# New_Project.net
KiCad netlist of a schematic drawn in EasyEDA
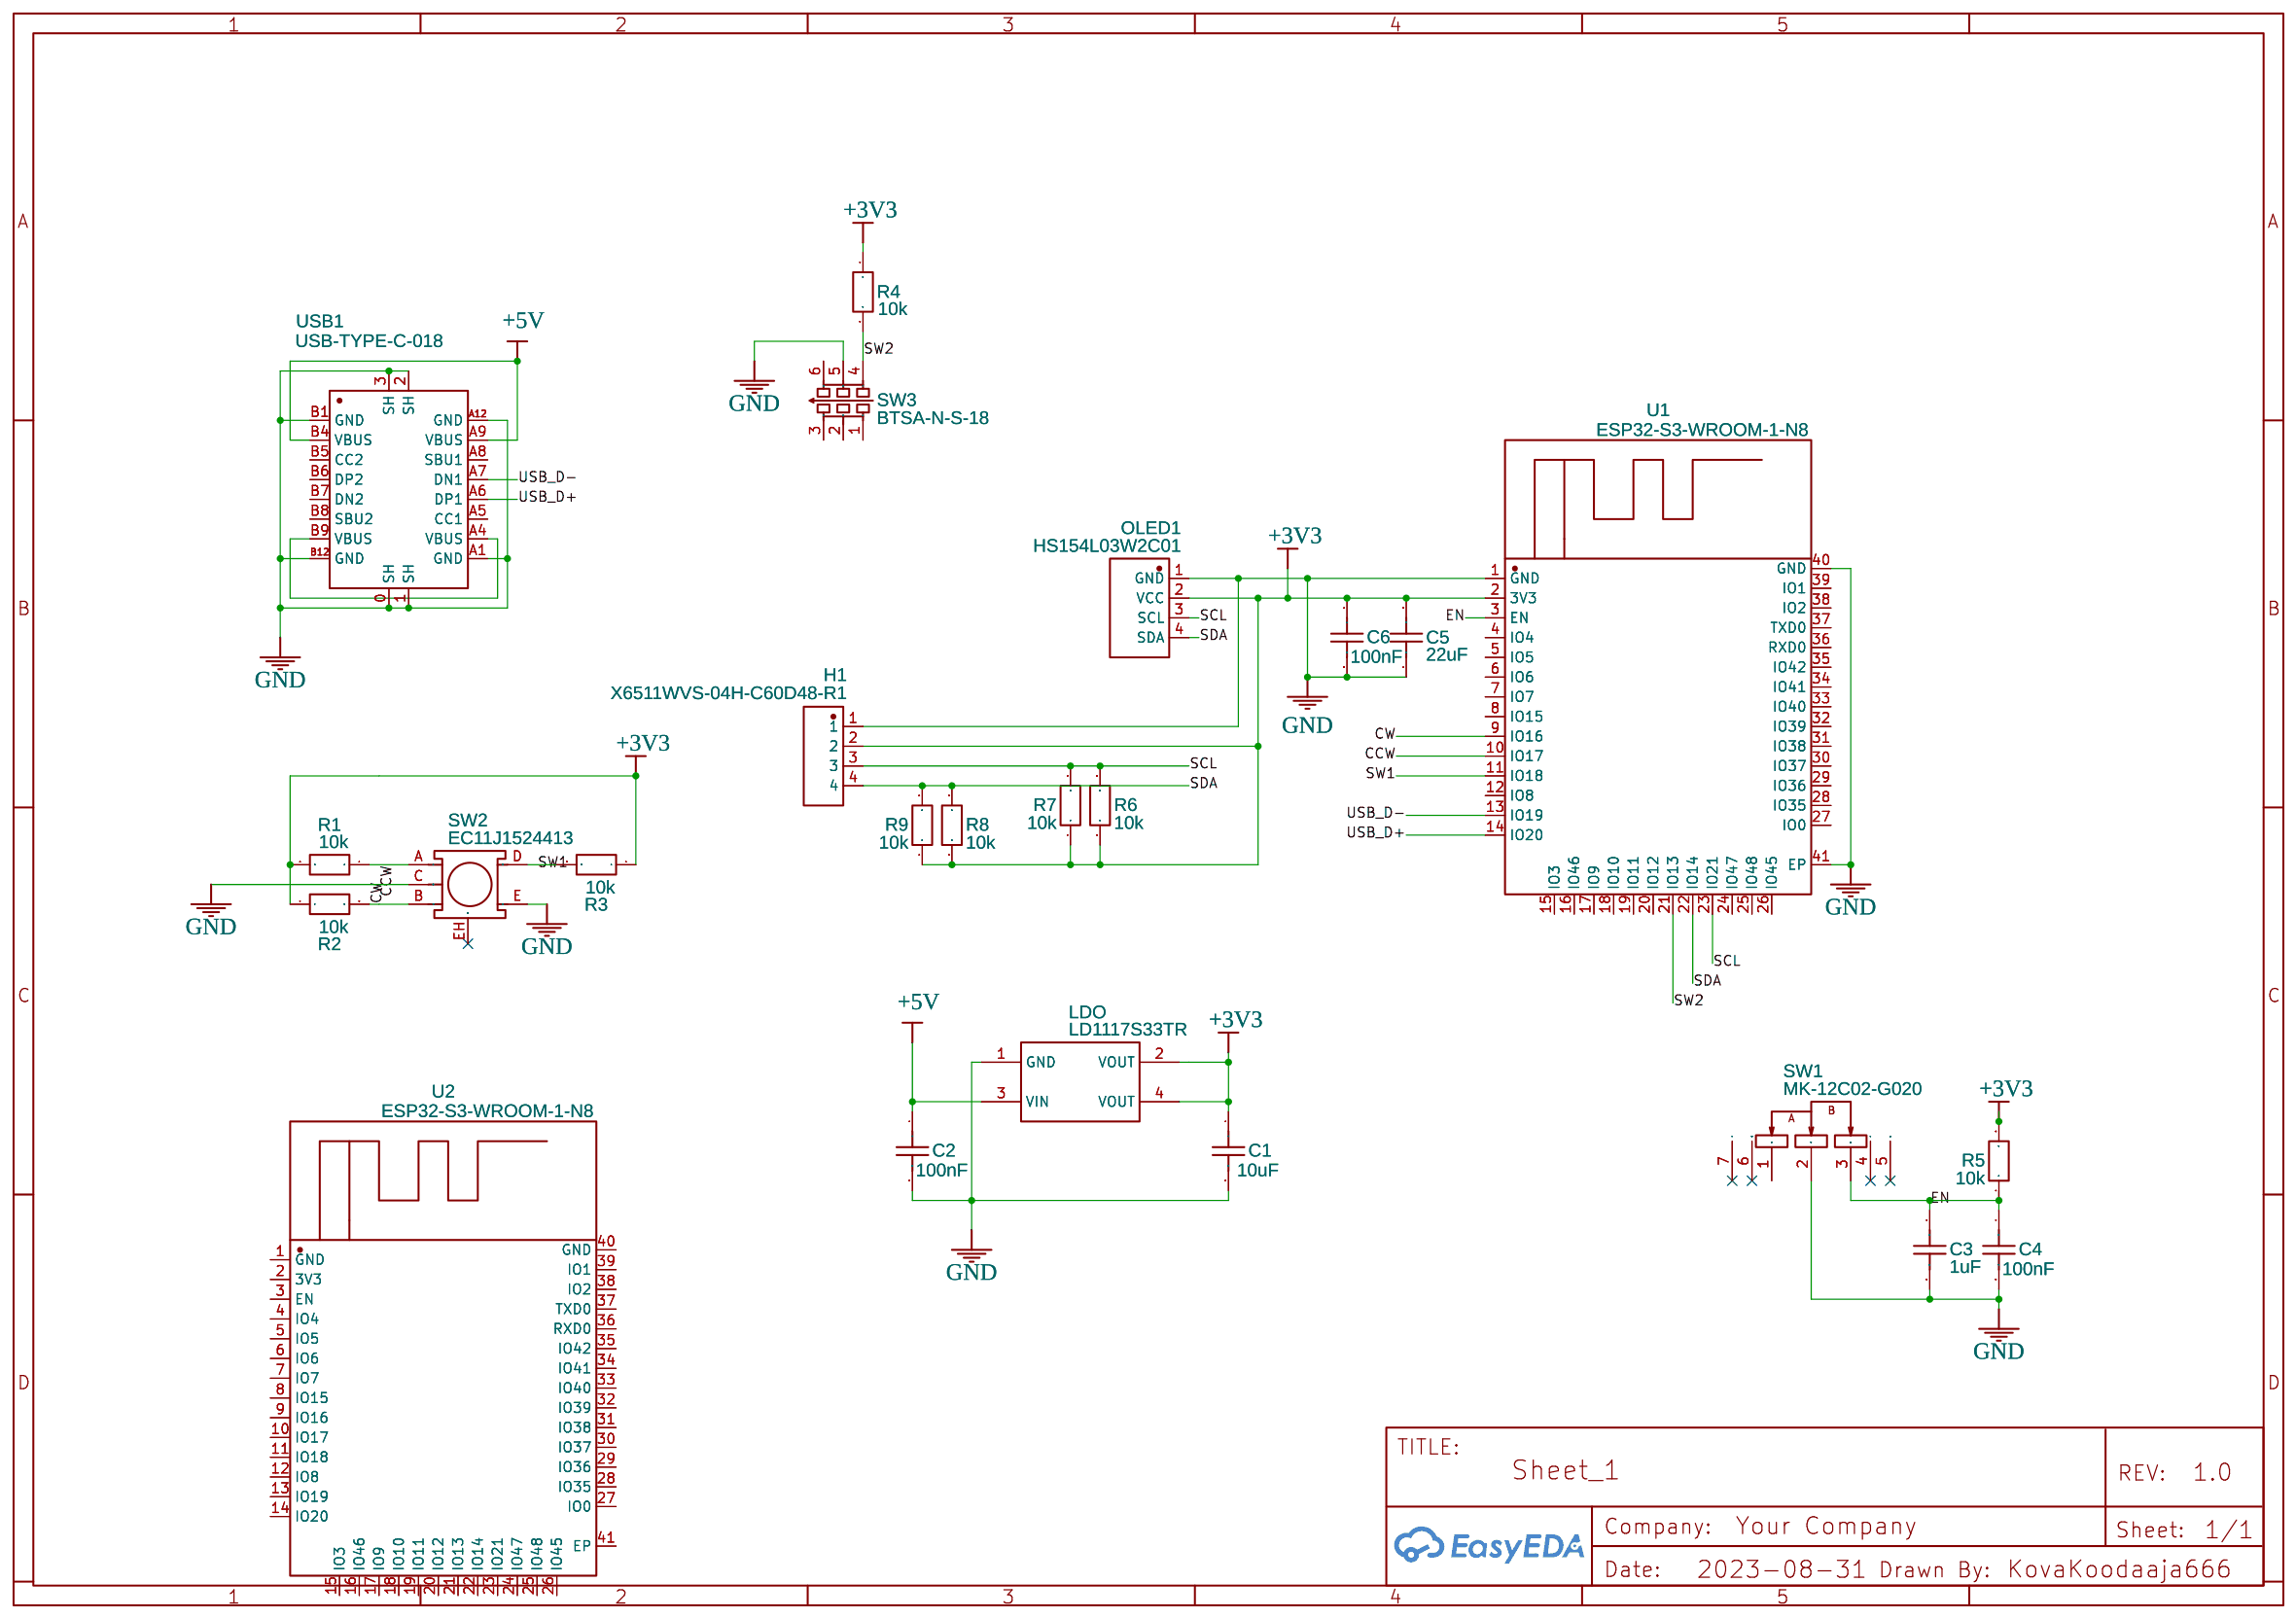
[diagram p0: schematic sheet]

(export (version "E")
  (design (tool "Eeschema 10.0.6"))
  (components
    (comp (ref "C1")
      (value "10uF")
      (fields
        (field (name "Manufacturer Part") "TCC0805X5R106K100FT")
        (field (name "Manufacturer") "CCTC(三环)")
      )
      (libsource (lib "") (part "TCC0805X5R106K100FT"))
    )
    (comp (ref "C2")
      (value "100nF")
      (fields (field (name "Manufacturer Part") "C0805B104K500NT") (field (name "Manufacturer") "TORCH(火炬)"))
      (libsource (lib "") (part "C0805B104K500NT"))
    )
    (comp (ref "C3")
      (value "1uF")
      (fields (field (name "Manufacturer") "FH(风华)"))
      (libsource (lib "") (part "0805B105K500NT_C215803"))
    )
    (comp (ref "C4")
      (value "100nF")
      (fields (field (name "Manufacturer Part") "C0805B104K500NT") (field (name "Manufacturer") "TORCH(火炬)"))
      (libsource (lib "") (part "C0805B104K500NT"))
    )
    (comp (ref "C5")
      (value "22uF")
      (fields
        (field (name "Manufacturer Part") "TCC0805X5R226M100FT")
        (field (name "Manufacturer") "CCTC(三环)")
      )
      (libsource (lib "") (part "TCC0805X5R226M100FT"))
    )
    (comp (ref "C6")
      (value "100nF")
      (fields (field (name "Manufacturer Part") "C0805B104K500NT") (field (name "Manufacturer") "TORCH(火炬)"))
      (libsource (lib "") (part "C0805B104K500NT"))
    )
    (comp (ref "H1")
      (value "X6511WVS-04H-C60D48-R1")
      (fields
        (field (name "Manufacturer Part") "X6511WVS-04H-C60D48R1")
        (field (name "Manufacturer") "XKB Connectivity(中国星坤)")
      )
      (libsource (lib "") (part "X6511WVS-04H-C60D48-R1"))
    )
    (comp (ref "LDO")
      (value "LD1117S33TR")
      (fields (field (name "Manufacturer") "ST(意法半导体)"))
      (libsource (lib "") (part "LD1117S33TR"))
    )
    (comp (ref "OLED1")
      (value "HS154L03W2C01")
      (fields (field (name "Manufacturer") "HS(汉昇)"))
      (libsource (lib "") (part "HS154L03W2C01"))
    )
    (comp (ref "R1")
      (value "10k")
      (fields (field (name "Manufacturer Part") "FRC0603J103TS") (field (name "Manufacturer") "FOJAN(富捷)"))
      (libsource (lib "") (part "FRC0603J103TS_3"))
    )
    (comp (ref "R2")
      (value "10k")
      (fields (field (name "Manufacturer Part") "FRC0603J103TS") (field (name "Manufacturer") "FOJAN(富捷)"))
      (libsource (lib "") (part "FRC0603J103TS_1"))
    )
    (comp (ref "R3")
      (value "10k")
      (fields (field (name "Manufacturer Part") "FRC0603J103TS") (field (name "Manufacturer") "FOJAN(富捷)"))
      (libsource (lib "") (part "FRC0603J103TS_3"))
    )
    (comp (ref "R4")
      (value "10k")
      (fields (field (name "Manufacturer Part") "FRC0603J103TS") (field (name "Manufacturer") "FOJAN(富捷)"))
      (libsource (lib "") (part "FRC0603J103TS"))
    )
    (comp (ref "R5")
      (value "10k")
      (fields (field (name "Manufacturer Part") "FRC0603J103TS") (field (name "Manufacturer") "FOJAN(富捷)"))
      (libsource (lib "") (part "FRC0603J103TS_2"))
    )
    (comp (ref "R6")
      (value "10k")
      (fields (field (name "Manufacturer Part") "FRC0603J103TS") (field (name "Manufacturer") "FOJAN(富捷)"))
      (libsource (lib "") (part "FRC0603J103TS_2"))
    )
    (comp (ref "R7")
      (value "10k")
      (fields (field (name "Manufacturer Part") "FRC0603J103TS") (field (name "Manufacturer") "FOJAN(富捷)"))
      (libsource (lib "") (part "FRC0603J103TS_2"))
    )
    (comp (ref "R8")
      (value "10k")
      (fields (field (name "Manufacturer Part") "FRC0603J103TS") (field (name "Manufacturer") "FOJAN(富捷)"))
      (libsource (lib "") (part "FRC0603J103TS_2"))
    )
    (comp (ref "R9")
      (value "10k")
      (fields (field (name "Manufacturer Part") "FRC0603J103TS") (field (name "Manufacturer") "FOJAN(富捷)"))
      (libsource (lib "") (part "FRC0603J103TS_2"))
    )
    (comp (ref "SW1")
      (value "MK-12C02-G020")
      (fields (field (name "Manufacturer") "G-Switch"))
      (libsource (lib "") (part "MK-12C02-G020"))
    )
    (comp (ref "SW2")
      (value "EC11J1524413")
      (fields (field (name "Manufacturer") "ALPSALPINE(阿尔卑斯阿尔派)"))
      (libsource (lib "") (part "EC11J1524413"))
    )
    (comp (ref "SW3")
      (value "BTSA-N-S-18")
      (fields (field (name "Manufacturer") "ROCPU Switches(台普)"))
      (libsource (lib "") (part "BTSA-N-S-18"))
    )
    (comp (ref "U1")
      (value "ESP32-S3-WROOM-1-N8")
      (fields (field (name "Manufacturer") "ESPRESSIF(乐鑫)"))
      (libsource (lib "") (part "ESP32-S3-WROOM-1-N8"))
    )
    (comp (ref "U2")
      (value "ESP32-S3-WROOM-1-N8")
      (fields (field (name "Manufacturer") "ESPRESSIF(乐鑫)"))
      (libsource (lib "") (part "ESP32-S3-WROOM-1-N8"))
    )
    (comp (ref "USB1")
      (value "USB-TYPE-C-018")
      (fields (field (name "Manufacturer") "DEALON(德艺隆)"))
      (libsource (lib "") (part "USB-TYPE-C-018"))
    )
  )
  (nets
    (net (code "1") (name "+3V3") (class "Default")
      (node (ref "C1") (pin "1") (pinfunction "1_1") (pintype "unspecified"))
      (node (ref "C5") (pin "2") (pinfunction "2_2") (pintype "unspecified"))
      (node (ref "C6") (pin "1") (pinfunction "1_1") (pintype "unspecified"))
      (node (ref "H1") (pin "2") (pinfunction "2_2") (pintype "unspecified"))
      (node (ref "LDO") (pin "2") (pinfunction "VOUT_2") (pintype "unspecified"))
      (node (ref "LDO") (pin "4") (pinfunction "VOUT_4") (pintype "unspecified"))
      (node (ref "OLED1") (pin "2") (pinfunction "VCC_2") (pintype "unspecified"))
      (node (ref "R1") (pin "2") (pinfunction "2_2") (pintype "unspecified"))
      (node (ref "R2") (pin "1") (pinfunction "1_1") (pintype "unspecified"))
      (node (ref "R3") (pin "1") (pinfunction "1_1") (pintype "unspecified"))
      (node (ref "R4") (pin "1") (pinfunction "1_1") (pintype "unspecified"))
      (node (ref "R5") (pin "2") (pinfunction "2_2") (pintype "unspecified"))
      (node (ref "R6") (pin "1") (pinfunction "1_1") (pintype "unspecified"))
      (node (ref "R7") (pin "1") (pinfunction "1_1") (pintype "unspecified"))
      (node (ref "R8") (pin "1") (pinfunction "1_1") (pintype "unspecified"))
      (node (ref "R9") (pin "1") (pinfunction "1_1") (pintype "unspecified"))
      (node (ref "U1") (pin "2") (pinfunction "3V3_2") (pintype "unspecified"))
    )
    (net (code "2") (name "+5V") (class "Default")
      (node (ref "C2") (pin "1") (pinfunction "1_1") (pintype "unspecified"))
      (node (ref "LDO") (pin "3") (pinfunction "VIN_3") (pintype "unspecified"))
      (node (ref "USB1") (pin "A9") (pinfunction "VBUS_A9") (pintype "unspecified"))
      (node (ref "USB1") (pin "B4") (pinfunction "VBUS_B4") (pintype "unspecified"))
    )
    (net (code "3") (name "/CCW") (class "Default")
      (node (ref "R1") (pin "1") (pinfunction "1_1") (pintype "unspecified"))
      (node (ref "SW2") (pin "A") (pinfunction "A_A") (pintype "unspecified"))
      (node (ref "U1") (pin "10") (pinfunction "IO17_10") (pintype "unspecified"))
    )
    (net (code "4") (name "/CW") (class "Default")
      (node (ref "R2") (pin "2") (pinfunction "2_2") (pintype "unspecified"))
      (node (ref "SW2") (pin "B") (pinfunction "B_B") (pintype "unspecified"))
      (node (ref "U1") (pin "9") (pinfunction "IO16_9") (pintype "unspecified"))
    )
    (net (code "5") (name "/EN") (class "Default")
      (node (ref "C3") (pin "1") (pinfunction "1_1") (pintype "unspecified"))
      (node (ref "C4") (pin "1") (pinfunction "1_1") (pintype "unspecified"))
      (node (ref "R5") (pin "1") (pinfunction "1_1") (pintype "unspecified"))
      (node (ref "SW1") (pin "3") (pinfunction "3_3") (pintype "unspecified"))
      (node (ref "U1") (pin "3") (pinfunction "EN_3") (pintype "unspecified"))
    )
    (net (code "6") (name "/SCL") (class "Default")
      (node (ref "H1") (pin "3") (pinfunction "3_3") (pintype "unspecified"))
      (node (ref "OLED1") (pin "3") (pinfunction "SCL_3") (pintype "unspecified"))
      (node (ref "R6") (pin "2") (pinfunction "2_2") (pintype "unspecified"))
      (node (ref "R7") (pin "2") (pinfunction "2_2") (pintype "unspecified"))
      (node (ref "U1") (pin "23") (pinfunction "IO21_23") (pintype "unspecified"))
    )
    (net (code "7") (name "/SDA") (class "Default")
      (node (ref "H1") (pin "4") (pinfunction "4_4") (pintype "unspecified"))
      (node (ref "OLED1") (pin "4") (pinfunction "SDA_4") (pintype "unspecified"))
      (node (ref "R8") (pin "2") (pinfunction "2_2") (pintype "unspecified"))
      (node (ref "R9") (pin "2") (pinfunction "2_2") (pintype "unspecified"))
      (node (ref "U1") (pin "22") (pinfunction "IO14_22") (pintype "unspecified"))
    )
    (net (code "8") (name "/SW1") (class "Default")
      (node (ref "R3") (pin "2") (pinfunction "2_2") (pintype "unspecified"))
      (node (ref "SW2") (pin "D") (pinfunction "D_D") (pintype "unspecified"))
      (node (ref "U1") (pin "11") (pinfunction "IO18_11") (pintype "unspecified"))
    )
    (net (code "9") (name "/SW2") (class "Default")
      (node (ref "R4") (pin "2") (pinfunction "2_2") (pintype "unspecified"))
      (node (ref "SW3") (pin "4") (pinfunction "4_4") (pintype "unspecified"))
      (node (ref "U1") (pin "21") (pinfunction "IO13_21") (pintype "unspecified"))
    )
    (net (code "10") (name "/USB_D+") (class "Default")
      (node (ref "U1") (pin "14") (pinfunction "IO20_14") (pintype "unspecified"))
      (node (ref "USB1") (pin "A6") (pinfunction "DP1_A6") (pintype "unspecified"))
    )
    (net (code "11") (name "/USB_D-") (class "Default")
      (node (ref "U1") (pin "13") (pinfunction "IO19_13") (pintype "unspecified"))
      (node (ref "USB1") (pin "A7") (pinfunction "DN1_A7") (pintype "unspecified"))
    )
    (net (code "12") (name "GND") (class "Default")
      (node (ref "C1") (pin "2") (pinfunction "2_2") (pintype "unspecified"))
      (node (ref "C2") (pin "2") (pinfunction "2_2") (pintype "unspecified"))
      (node (ref "C3") (pin "2") (pinfunction "2_2") (pintype "unspecified"))
      (node (ref "C4") (pin "2") (pinfunction "2_2") (pintype "unspecified"))
      (node (ref "C5") (pin "1") (pinfunction "1_1") (pintype "unspecified"))
      (node (ref "C6") (pin "2") (pinfunction "2_2") (pintype "unspecified"))
      (node (ref "H1") (pin "1") (pinfunction "1_1") (pintype "unspecified"))
      (node (ref "LDO") (pin "1") (pinfunction "GND_1") (pintype "unspecified"))
      (node (ref "OLED1") (pin "1") (pinfunction "GND_1") (pintype "unspecified"))
      (node (ref "SW1") (pin "2") (pinfunction "2_2") (pintype "unspecified"))
      (node (ref "SW2") (pin "C") (pinfunction "C_C") (pintype "unspecified"))
      (node (ref "SW2") (pin "E") (pinfunction "E_E") (pintype "unspecified"))
      (node (ref "SW3") (pin "5") (pinfunction "5_5") (pintype "unspecified"))
      (node (ref "U1") (pin "1") (pinfunction "GND_1") (pintype "unspecified"))
      (node (ref "U1") (pin "40") (pinfunction "GND_40") (pintype "unspecified"))
      (node (ref "U1") (pin "41") (pinfunction "EP_41") (pintype "unspecified"))
      (node (ref "USB1") (pin "0") (pinfunction "SH_0") (pintype "unspecified"))
      (node (ref "USB1") (pin "1") (pinfunction "SH_1") (pintype "unspecified"))
      (node (ref "USB1") (pin "2") (pinfunction "SH_2") (pintype "unspecified"))
      (node (ref "USB1") (pin "3") (pinfunction "SH_3") (pintype "unspecified"))
      (node (ref "USB1") (pin "A1") (pinfunction "GND_A1") (pintype "unspecified"))
      (node (ref "USB1") (pin "A12") (pinfunction "GND_A12") (pintype "unspecified"))
      (node (ref "USB1") (pin "B1") (pinfunction "GND_B1") (pintype "unspecified"))
      (node (ref "USB1") (pin "B12") (pinfunction "GND_B12") (pintype "unspecified"))
    )
    (net (code "13") (name "Net-(USB1-VBUS-PadA4)") (class "Default")
      (node (ref "USB1") (pin "A4") (pinfunction "VBUS_A4") (pintype "unspecified"))
      (node (ref "USB1") (pin "B9") (pinfunction "VBUS_B9") (pintype "unspecified"))
    )
    (net (code "14") (name "unconnected-(SW1-Pad1)") (class "Default")
      (node (ref "SW1") (pin "1") (pinfunction "1_1") (pintype "unspecified"))
    )
    (net (code "15") (name "unconnected-(SW1-Pad4)") (class "Default")
      (node (ref "SW1") (pin "4") (pinfunction "4_4") (pintype "unspecified+no_connect"))
    )
    (net (code "16") (name "unconnected-(SW1-Pad5)") (class "Default")
      (node (ref "SW1") (pin "5") (pinfunction "5_5") (pintype "unspecified+no_connect"))
    )
    (net (code "17") (name "unconnected-(SW1-Pad6)") (class "Default")
      (node (ref "SW1") (pin "6") (pinfunction "6_6") (pintype "unspecified+no_connect"))
    )
    (net (code "18") (name "unconnected-(SW1-Pad7)") (class "Default")
      (node (ref "SW1") (pin "7") (pinfunction "7_7") (pintype "unspecified+no_connect"))
    )
    (net (code "19") (name "unconnected-(SW2-PadEH)") (class "Default")
      (node (ref "SW2") (pin "EH") (pinfunction "EH_EH") (pintype "unspecified+no_connect"))
    )
    (net (code "20") (name "unconnected-(SW3-Pad1)") (class "Default")
      (node (ref "SW3") (pin "1") (pinfunction "1_1") (pintype "unspecified"))
    )
    (net (code "21") (name "unconnected-(SW3-Pad2)") (class "Default")
      (node (ref "SW3") (pin "2") (pinfunction "2_2") (pintype "unspecified"))
    )
    (net (code "22") (name "unconnected-(SW3-Pad3)") (class "Default")
      (node (ref "SW3") (pin "3") (pinfunction "3_3") (pintype "unspecified"))
    )
    (net (code "23") (name "unconnected-(SW3-Pad6)") (class "Default")
      (node (ref "SW3") (pin "6") (pinfunction "6_6") (pintype "unspecified"))
    )
    (net (code "24") (name "unconnected-(U1-IO0-Pad27)") (class "Default")
      (node (ref "U1") (pin "27") (pinfunction "IO0_27") (pintype "unspecified"))
    )
    (net (code "25") (name "unconnected-(U1-IO1-Pad39)") (class "Default")
      (node (ref "U1") (pin "39") (pinfunction "IO1_39") (pintype "unspecified"))
    )
    (net (code "26") (name "unconnected-(U1-IO2-Pad38)") (class "Default")
      (node (ref "U1") (pin "38") (pinfunction "IO2_38") (pintype "unspecified"))
    )
    (net (code "27") (name "unconnected-(U1-IO3-Pad15)") (class "Default")
      (node (ref "U1") (pin "15") (pinfunction "IO3_15") (pintype "unspecified"))
    )
    (net (code "28") (name "unconnected-(U1-IO4-Pad4)") (class "Default")
      (node (ref "U1") (pin "4") (pinfunction "IO4_4") (pintype "unspecified"))
    )
    (net (code "29") (name "unconnected-(U1-IO5-Pad5)") (class "Default")
      (node (ref "U1") (pin "5") (pinfunction "IO5_5") (pintype "unspecified"))
    )
    (net (code "30") (name "unconnected-(U1-IO6-Pad6)") (class "Default")
      (node (ref "U1") (pin "6") (pinfunction "IO6_6") (pintype "unspecified"))
    )
    (net (code "31") (name "unconnected-(U1-IO7-Pad7)") (class "Default")
      (node (ref "U1") (pin "7") (pinfunction "IO7_7") (pintype "unspecified"))
    )
    (net (code "32") (name "unconnected-(U1-IO8-Pad12)") (class "Default")
      (node (ref "U1") (pin "12") (pinfunction "IO8_12") (pintype "unspecified"))
    )
    (net (code "33") (name "unconnected-(U1-IO9-Pad17)") (class "Default")
      (node (ref "U1") (pin "17") (pinfunction "IO9_17") (pintype "unspecified"))
    )
    (net (code "34") (name "unconnected-(U1-IO10-Pad18)") (class "Default")
      (node (ref "U1") (pin "18") (pinfunction "IO10_18") (pintype "unspecified"))
    )
    (net (code "35") (name "unconnected-(U1-IO11-Pad19)") (class "Default")
      (node (ref "U1") (pin "19") (pinfunction "IO11_19") (pintype "unspecified"))
    )
    (net (code "36") (name "unconnected-(U1-IO12-Pad20)") (class "Default")
      (node (ref "U1") (pin "20") (pinfunction "IO12_20") (pintype "unspecified"))
    )
    (net (code "37") (name "unconnected-(U1-IO15-Pad8)") (class "Default")
      (node (ref "U1") (pin "8") (pinfunction "IO15_8") (pintype "unspecified"))
    )
    (net (code "38") (name "unconnected-(U1-IO35-Pad28)") (class "Default")
      (node (ref "U1") (pin "28") (pinfunction "IO35_28") (pintype "unspecified"))
    )
    (net (code "39") (name "unconnected-(U1-IO36-Pad29)") (class "Default")
      (node (ref "U1") (pin "29") (pinfunction "IO36_29") (pintype "unspecified"))
    )
    (net (code "40") (name "unconnected-(U1-IO37-Pad30)") (class "Default")
      (node (ref "U1") (pin "30") (pinfunction "IO37_30") (pintype "unspecified"))
    )
    (net (code "41") (name "unconnected-(U1-IO38-Pad31)") (class "Default")
      (node (ref "U1") (pin "31") (pinfunction "IO38_31") (pintype "unspecified"))
    )
    (net (code "42") (name "unconnected-(U1-IO39-Pad32)") (class "Default")
      (node (ref "U1") (pin "32") (pinfunction "IO39_32") (pintype "unspecified"))
    )
    (net (code "43") (name "unconnected-(U1-IO40-Pad33)") (class "Default")
      (node (ref "U1") (pin "33") (pinfunction "IO40_33") (pintype "unspecified"))
    )
    (net (code "44") (name "unconnected-(U1-IO41-Pad34)") (class "Default")
      (node (ref "U1") (pin "34") (pinfunction "IO41_34") (pintype "unspecified"))
    )
    (net (code "45") (name "unconnected-(U1-IO42-Pad35)") (class "Default")
      (node (ref "U1") (pin "35") (pinfunction "IO42_35") (pintype "unspecified"))
    )
    (net (code "46") (name "unconnected-(U1-IO45-Pad26)") (class "Default")
      (node (ref "U1") (pin "26") (pinfunction "IO45_26") (pintype "unspecified"))
    )
    (net (code "47") (name "unconnected-(U1-IO46-Pad16)") (class "Default")
      (node (ref "U1") (pin "16") (pinfunction "IO46_16") (pintype "unspecified"))
    )
    (net (code "48") (name "unconnected-(U1-IO47-Pad24)") (class "Default")
      (node (ref "U1") (pin "24") (pinfunction "IO47_24") (pintype "unspecified"))
    )
    (net (code "49") (name "unconnected-(U1-IO48-Pad25)") (class "Default")
      (node (ref "U1") (pin "25") (pinfunction "IO48_25") (pintype "unspecified"))
    )
    (net (code "50") (name "unconnected-(U1-RXD0-Pad36)") (class "Default")
      (node (ref "U1") (pin "36") (pinfunction "RXD0_36") (pintype "unspecified"))
    )
    (net (code "51") (name "unconnected-(U1-TXD0-Pad37)") (class "Default")
      (node (ref "U1") (pin "37") (pinfunction "TXD0_37") (pintype "unspecified"))
    )
    (net (code "52") (name "unconnected-(U2-3V3-Pad2)") (class "Default")
      (node (ref "U2") (pin "2") (pinfunction "3V3_2") (pintype "unspecified"))
    )
    (net (code "53") (name "unconnected-(U2-EN-Pad3)") (class "Default")
      (node (ref "U2") (pin "3") (pinfunction "EN_3") (pintype "unspecified"))
    )
    (net (code "54") (name "unconnected-(U2-EP-Pad41)") (class "Default")
      (node (ref "U2") (pin "41") (pinfunction "EP_41") (pintype "unspecified"))
    )
    (net (code "55") (name "unconnected-(U2-GND-Pad1)") (class "Default")
      (node (ref "U2") (pin "1") (pinfunction "GND_1") (pintype "unspecified"))
    )
    (net (code "56") (name "unconnected-(U2-GND-Pad40)") (class "Default")
      (node (ref "U2") (pin "40") (pinfunction "GND_40") (pintype "unspecified"))
    )
    (net (code "57") (name "unconnected-(U2-IO0-Pad27)") (class "Default")
      (node (ref "U2") (pin "27") (pinfunction "IO0_27") (pintype "unspecified"))
    )
    (net (code "58") (name "unconnected-(U2-IO1-Pad39)") (class "Default")
      (node (ref "U2") (pin "39") (pinfunction "IO1_39") (pintype "unspecified"))
    )
    (net (code "59") (name "unconnected-(U2-IO2-Pad38)") (class "Default")
      (node (ref "U2") (pin "38") (pinfunction "IO2_38") (pintype "unspecified"))
    )
    (net (code "60") (name "unconnected-(U2-IO3-Pad15)") (class "Default")
      (node (ref "U2") (pin "15") (pinfunction "IO3_15") (pintype "unspecified"))
    )
    (net (code "61") (name "unconnected-(U2-IO4-Pad4)") (class "Default")
      (node (ref "U2") (pin "4") (pinfunction "IO4_4") (pintype "unspecified"))
    )
    (net (code "62") (name "unconnected-(U2-IO5-Pad5)") (class "Default")
      (node (ref "U2") (pin "5") (pinfunction "IO5_5") (pintype "unspecified"))
    )
    (net (code "63") (name "unconnected-(U2-IO6-Pad6)") (class "Default")
      (node (ref "U2") (pin "6") (pinfunction "IO6_6") (pintype "unspecified"))
    )
    (net (code "64") (name "unconnected-(U2-IO7-Pad7)") (class "Default")
      (node (ref "U2") (pin "7") (pinfunction "IO7_7") (pintype "unspecified"))
    )
    (net (code "65") (name "unconnected-(U2-IO8-Pad12)") (class "Default")
      (node (ref "U2") (pin "12") (pinfunction "IO8_12") (pintype "unspecified"))
    )
    (net (code "66") (name "unconnected-(U2-IO9-Pad17)") (class "Default")
      (node (ref "U2") (pin "17") (pinfunction "IO9_17") (pintype "unspecified"))
    )
    (net (code "67") (name "unconnected-(U2-IO10-Pad18)") (class "Default")
      (node (ref "U2") (pin "18") (pinfunction "IO10_18") (pintype "unspecified"))
    )
    (net (code "68") (name "unconnected-(U2-IO11-Pad19)") (class "Default")
      (node (ref "U2") (pin "19") (pinfunction "IO11_19") (pintype "unspecified"))
    )
    (net (code "69") (name "unconnected-(U2-IO12-Pad20)") (class "Default")
      (node (ref "U2") (pin "20") (pinfunction "IO12_20") (pintype "unspecified"))
    )
    (net (code "70") (name "unconnected-(U2-IO13-Pad21)") (class "Default")
      (node (ref "U2") (pin "21") (pinfunction "IO13_21") (pintype "unspecified"))
    )
    (net (code "71") (name "unconnected-(U2-IO14-Pad22)") (class "Default")
      (node (ref "U2") (pin "22") (pinfunction "IO14_22") (pintype "unspecified"))
    )
    (net (code "72") (name "unconnected-(U2-IO15-Pad8)") (class "Default")
      (node (ref "U2") (pin "8") (pinfunction "IO15_8") (pintype "unspecified"))
    )
    (net (code "73") (name "unconnected-(U2-IO16-Pad9)") (class "Default")
      (node (ref "U2") (pin "9") (pinfunction "IO16_9") (pintype "unspecified"))
    )
    (net (code "74") (name "unconnected-(U2-IO17-Pad10)") (class "Default")
      (node (ref "U2") (pin "10") (pinfunction "IO17_10") (pintype "unspecified"))
    )
    (net (code "75") (name "unconnected-(U2-IO18-Pad11)") (class "Default")
      (node (ref "U2") (pin "11") (pinfunction "IO18_11") (pintype "unspecified"))
    )
    (net (code "76") (name "unconnected-(U2-IO19-Pad13)") (class "Default")
      (node (ref "U2") (pin "13") (pinfunction "IO19_13") (pintype "unspecified"))
    )
    (net (code "77") (name "unconnected-(U2-IO20-Pad14)") (class "Default")
      (node (ref "U2") (pin "14") (pinfunction "IO20_14") (pintype "unspecified"))
    )
    (net (code "78") (name "unconnected-(U2-IO21-Pad23)") (class "Default")
      (node (ref "U2") (pin "23") (pinfunction "IO21_23") (pintype "unspecified"))
    )
    (net (code "79") (name "unconnected-(U2-IO35-Pad28)") (class "Default")
      (node (ref "U2") (pin "28") (pinfunction "IO35_28") (pintype "unspecified"))
    )
    (net (code "80") (name "unconnected-(U2-IO36-Pad29)") (class "Default")
      (node (ref "U2") (pin "29") (pinfunction "IO36_29") (pintype "unspecified"))
    )
    (net (code "81") (name "unconnected-(U2-IO37-Pad30)") (class "Default")
      (node (ref "U2") (pin "30") (pinfunction "IO37_30") (pintype "unspecified"))
    )
    (net (code "82") (name "unconnected-(U2-IO38-Pad31)") (class "Default")
      (node (ref "U2") (pin "31") (pinfunction "IO38_31") (pintype "unspecified"))
    )
    (net (code "83") (name "unconnected-(U2-IO39-Pad32)") (class "Default")
      (node (ref "U2") (pin "32") (pinfunction "IO39_32") (pintype "unspecified"))
    )
    (net (code "84") (name "unconnected-(U2-IO40-Pad33)") (class "Default")
      (node (ref "U2") (pin "33") (pinfunction "IO40_33") (pintype "unspecified"))
    )
    (net (code "85") (name "unconnected-(U2-IO41-Pad34)") (class "Default")
      (node (ref "U2") (pin "34") (pinfunction "IO41_34") (pintype "unspecified"))
    )
    (net (code "86") (name "unconnected-(U2-IO42-Pad35)") (class "Default")
      (node (ref "U2") (pin "35") (pinfunction "IO42_35") (pintype "unspecified"))
    )
    (net (code "87") (name "unconnected-(U2-IO45-Pad26)") (class "Default")
      (node (ref "U2") (pin "26") (pinfunction "IO45_26") (pintype "unspecified"))
    )
    (net (code "88") (name "unconnected-(U2-IO46-Pad16)") (class "Default")
      (node (ref "U2") (pin "16") (pinfunction "IO46_16") (pintype "unspecified"))
    )
    (net (code "89") (name "unconnected-(U2-IO47-Pad24)") (class "Default")
      (node (ref "U2") (pin "24") (pinfunction "IO47_24") (pintype "unspecified"))
    )
    (net (code "90") (name "unconnected-(U2-IO48-Pad25)") (class "Default")
      (node (ref "U2") (pin "25") (pinfunction "IO48_25") (pintype "unspecified"))
    )
    (net (code "91") (name "unconnected-(U2-RXD0-Pad36)") (class "Default")
      (node (ref "U2") (pin "36") (pinfunction "RXD0_36") (pintype "unspecified"))
    )
    (net (code "92") (name "unconnected-(U2-TXD0-Pad37)") (class "Default")
      (node (ref "U2") (pin "37") (pinfunction "TXD0_37") (pintype "unspecified"))
    )
    (net (code "93") (name "unconnected-(USB1-CC1-PadA5)") (class "Default")
      (node (ref "USB1") (pin "A5") (pinfunction "CC1_A5") (pintype "unspecified"))
    )
    (net (code "94") (name "unconnected-(USB1-CC2-PadB5)") (class "Default")
      (node (ref "USB1") (pin "B5") (pinfunction "CC2_B5") (pintype "unspecified"))
    )
    (net (code "95") (name "unconnected-(USB1-DN2-PadB7)") (class "Default")
      (node (ref "USB1") (pin "B7") (pinfunction "DN2_B7") (pintype "unspecified"))
    )
    (net (code "96") (name "unconnected-(USB1-DP2-PadB6)") (class "Default")
      (node (ref "USB1") (pin "B6") (pinfunction "DP2_B6") (pintype "unspecified"))
    )
    (net (code "97") (name "unconnected-(USB1-SBU1-PadA8)") (class "Default")
      (node (ref "USB1") (pin "A8") (pinfunction "SBU1_A8") (pintype "unspecified"))
    )
    (net (code "98") (name "unconnected-(USB1-SBU2-PadB8)") (class "Default")
      (node (ref "USB1") (pin "B8") (pinfunction "SBU2_B8") (pintype "unspecified"))
    )
  )
)
